# Lilypad_Schematic_1.net
KiCad netlist of a schematic drawn in Altium Designer
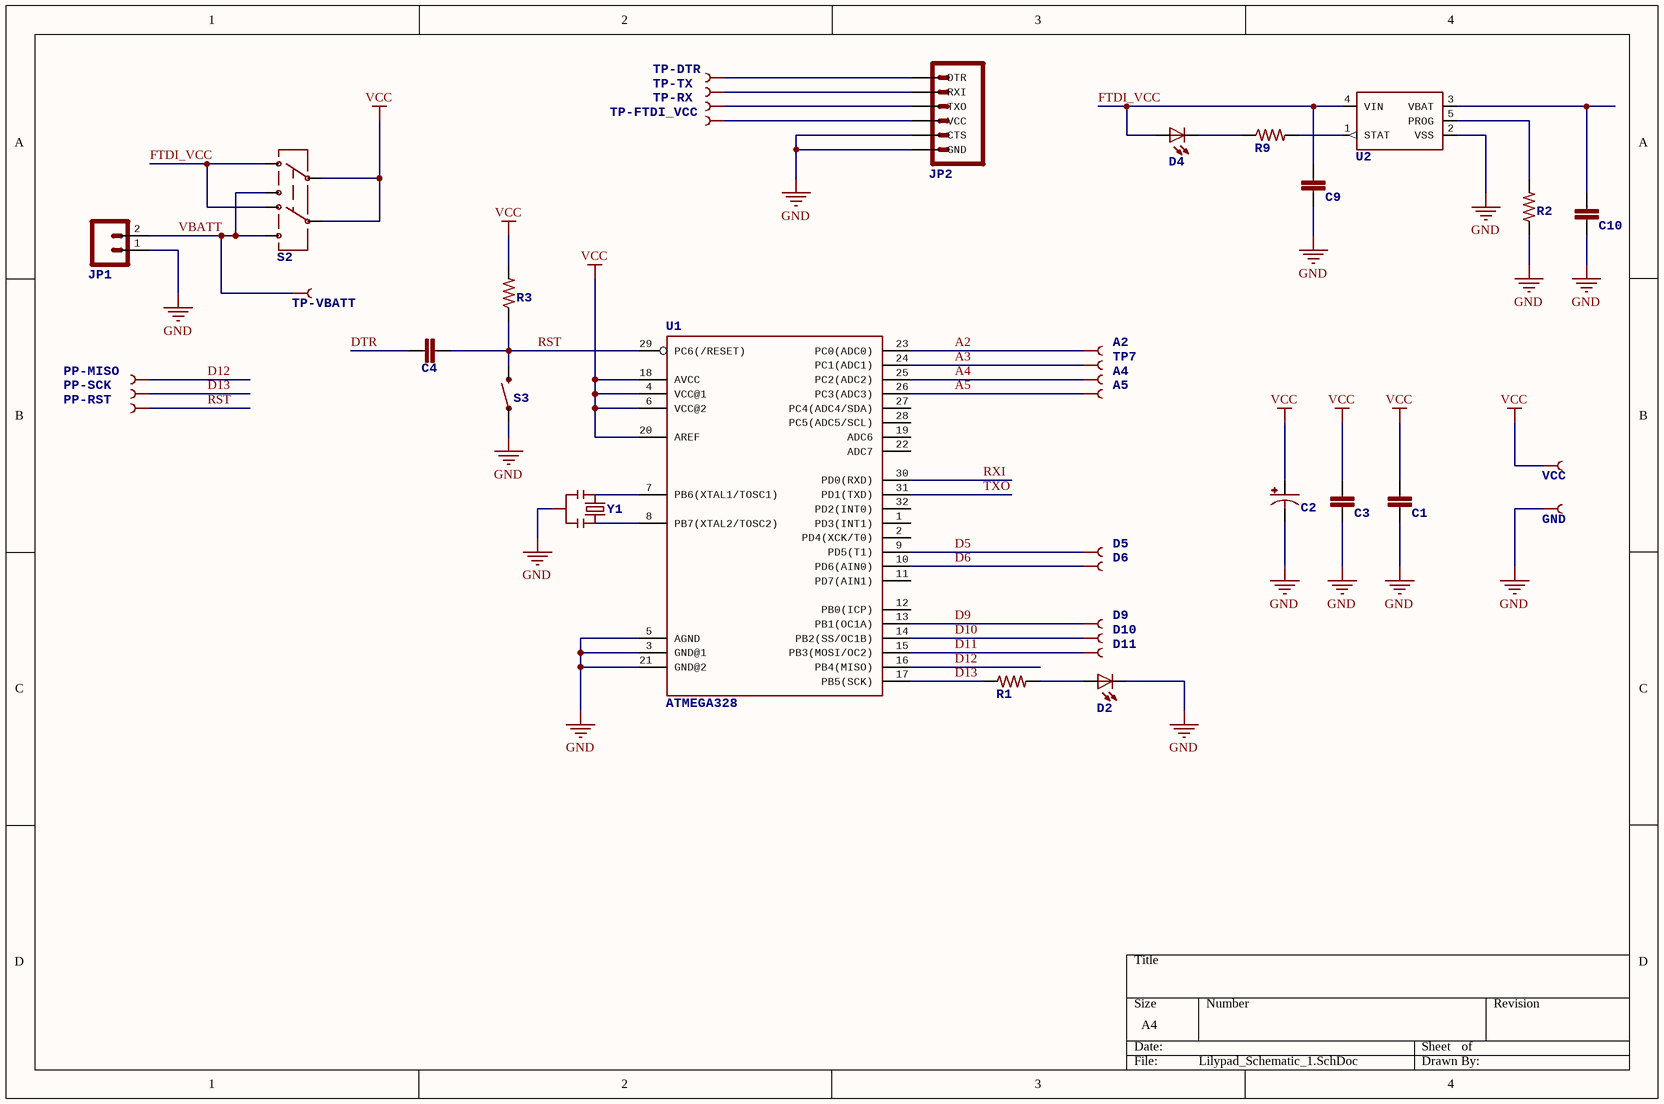
[diagram p0: Lilypad_Schematic_1.SchDoc]

(export (version "E")
  (design (tool "Eeschema 10.0.6"))
  (components
    (comp (ref "A2")
      (value "CONN")
      (footprint "PETAL-LONG-2")
      (libsource (lib "LilyPad Simple v2") (part "CONN"))
    )
    (comp (ref "A4")
      (value "CONN")
      (footprint "PETAL-LONG-2")
      (libsource (lib "LilyPad Simple v2") (part "CONN"))
    )
    (comp (ref "A5")
      (value "CONN")
      (footprint "PETAL-LONG-2")
      (libsource (lib "LilyPad Simple v2") (part "CONN"))
    )
    (comp (ref "C1")
      (value "CAP0402-CAP")
      (footprint "0402-CAP")
      (libsource (lib "LilyPad Simple v2") (part "CAP0402-CAP"))
    )
    (comp (ref "C2")
      (value "CAP_POL3528")
      (footprint "EIA3528")
      (libsource (lib "LilyPad Simple v2") (part "CAP_POL3528"))
    )
    (comp (ref "C3")
      (value "CAP0402-CAP")
      (footprint "0402-CAP")
      (libsource (lib "LilyPad Simple v2") (part "CAP0402-CAP"))
    )
    (comp (ref "C4") (value "CAP0402-CAP") (footprint "0402-CAP") (libsource (lib "") (part "CAP0402-CAP_1")))
    (comp (ref "C9")
      (value "CAP0402-CAP")
      (footprint "0402-CAP")
      (libsource (lib "LilyPad Simple v2") (part "CAP0402-CAP"))
    )
    (comp (ref "C10")
      (value "CAP0402-CAP")
      (footprint "0402-CAP")
      (libsource (lib "LilyPad Simple v2") (part "CAP0402-CAP"))
    )
    (comp (ref "D2")
      (value "LED0603")
      (footprint "LED-0603")
      (libsource (lib "LilyPad Simple v2") (part "LED0603"))
    )
    (comp (ref "D4")
      (value "LED0603")
      (footprint "LED-0603")
      (libsource (lib "LilyPad Simple v2") (part "LED0603"))
    )
    (comp (ref "D5")
      (value "CONN")
      (footprint "PETAL-LONG-2")
      (libsource (lib "LilyPad Simple v2") (part "CONN"))
    )
    (comp (ref "D6")
      (value "CONN")
      (footprint "PETAL-LONG-2")
      (libsource (lib "LilyPad Simple v2") (part "CONN"))
    )
    (comp (ref "D9")
      (value "CONN")
      (footprint "PETAL-LONG-2")
      (libsource (lib "LilyPad Simple v2") (part "CONN"))
    )
    (comp (ref "D10")
      (value "CONN")
      (footprint "PETAL-LONG-2")
      (libsource (lib "LilyPad Simple v2") (part "CONN"))
    )
    (comp (ref "D11")
      (value "CONN")
      (footprint "PETAL-LONG-2")
      (libsource (lib "LilyPad Simple v2") (part "CONN"))
    )
    (comp (ref "GND")
      (value "CONN")
      (footprint "PETAL-LONG-2")
      (libsource (lib "LilyPad Simple v2") (part "CONN"))
    )
    (comp (ref "JP1")
      (value "M02-JST-2MM-SMT")
      (footprint "JST-2-SMD")
      (libsource (lib "LilyPad Simple v2") (part "M02-JST-2MM-SMT"))
    )
    (comp (ref "JP2")
      (value "ARDUINO_SERIAL_PROGRAMSMD")
      (footprint "1X06-SMD")
      (libsource (lib "LilyPad Simple v2") (part "ARDUINO_SERIAL_PROGRAMSMD"))
    )
    (comp (ref "PP-MISO")
      (value "TEST-POINT3X5")
      (footprint "PAD.03X.05")
      (libsource (lib "LilyPad Simple v2") (part "TEST-POINT3X5"))
    )
    (comp (ref "PP-RST")
      (value "TEST-POINT3X5")
      (footprint "PAD.03X.05")
      (libsource (lib "LilyPad Simple v2") (part "TEST-POINT3X5"))
    )
    (comp (ref "PP-SCK")
      (value "TEST-POINT3X5")
      (footprint "PAD.03X.05")
      (libsource (lib "LilyPad Simple v2") (part "TEST-POINT3X5"))
    )
    (comp (ref "R1")
      (value "RESISTOR0402-RES")
      (footprint "0402-RES")
      (libsource (lib "LilyPad Simple v2") (part "RESISTOR0402-RES"))
    )
    (comp (ref "R2")
      (value "RESISTOR0402-RES")
      (footprint "0402-RES")
      (libsource (lib "LilyPad Simple v2") (part "RESISTOR0402-RES"))
    )
    (comp (ref "R3")
      (value "RESISTOR0402-RES")
      (footprint "0402-RES")
      (libsource (lib "LilyPad Simple v2") (part "RESISTOR0402-RES"))
    )
    (comp (ref "R9")
      (value "RESISTOR0402-RES")
      (footprint "0402-RES")
      (libsource (lib "LilyPad Simple v2") (part "RESISTOR0402-RES"))
    )
    (comp (ref "S2")
      (value "AYZ0202")
      (footprint "AYZ0202")
      (libsource (lib "LilyPad Simple v2") (part "AYZ0202"))
    )
    (comp (ref "S3")
      (value "SWITCH-MOMENTARY-2SMD-2")
      (footprint "TACTILE_SWITCH_SMD-2")
      (libsource (lib "LilyPad Simple v2") (part "SWITCH-MOMENTARY-2SMD-2"))
    )
    (comp (ref "TP-DTR")
      (value "TEST-POINT3X5")
      (footprint "PAD.03X.05")
      (libsource (lib "LilyPad Simple v2") (part "TEST-POINT3X5"))
    )
    (comp (ref "TP-FTDI_VCC")
      (value "TEST-POINT3X5")
      (footprint "PAD.03X.05")
      (libsource (lib "LilyPad Simple v2") (part "TEST-POINT3X5"))
    )
    (comp (ref "TP-RX")
      (value "TEST-POINT3X5")
      (footprint "PAD.03X.05")
      (libsource (lib "LilyPad Simple v2") (part "TEST-POINT3X5"))
    )
    (comp (ref "TP-TX")
      (value "TEST-POINT3X5")
      (footprint "PAD.03X.05")
      (libsource (lib "LilyPad Simple v2") (part "TEST-POINT3X5"))
    )
    (comp (ref "TP-VBATT")
      (value "TEST-POINT3X5")
      (footprint "PAD.03X.05")
      (libsource (lib "LilyPad Simple v2") (part "TEST-POINT3X5"))
    )
    (comp (ref "TP7")
      (value "CONN")
      (footprint "PETAL-LONG-2")
      (libsource (lib "LilyPad Simple v2") (part "CONN"))
    )
    (comp (ref "U1")
      (value "ATMEGA328")
      (footprint "TQFP32-08")
      (libsource (lib "LilyPad Simple v2") (part "ATMEGA328"))
    )
    (comp (ref "U2")
      (value "MCP73831")
      (footprint "SOT23-5")
      (libsource (lib "LilyPad Simple v2") (part "MCP73831"))
    )
    (comp (ref "VCC")
      (value "CONN")
      (footprint "PETAL-LONG-2")
      (libsource (lib "LilyPad Simple v2") (part "CONN"))
    )
    (comp (ref "Y1")
      (value "RESONATORSMD")
      (footprint "RESONATOR-SMD")
      (libsource (lib "LilyPad Simple v2") (part "RESONATORSMD"))
    )
  )
  (nets
    (net (code "1") (name "/A2") (class "Default")
      (node (ref "A2") (pin "1") (pinfunction "1_1") (pintype "passive"))
      (node (ref "U1") (pin "23") (pinfunction "PC0(ADC0)_23") (pintype "passive"))
    )
    (net (code "2") (name "/A3") (class "Default")
      (node (ref "TP7") (pin "1") (pinfunction "1_1") (pintype "passive"))
      (node (ref "U1") (pin "24") (pinfunction "PC1(ADC1)_24") (pintype "passive"))
    )
    (net (code "3") (name "/A4") (class "Default")
      (node (ref "A4") (pin "1") (pinfunction "1_1") (pintype "passive"))
      (node (ref "U1") (pin "25") (pinfunction "PC2(ADC2)_25") (pintype "passive"))
    )
    (net (code "4") (name "/A5") (class "Default")
      (node (ref "A5") (pin "1") (pinfunction "1_1") (pintype "passive"))
      (node (ref "U1") (pin "26") (pinfunction "PC3(ADC3)_26") (pintype "passive"))
    )
    (net (code "5") (name "/D5") (class "Default")
      (node (ref "D5") (pin "1") (pinfunction "1_1") (pintype "passive"))
      (node (ref "U1") (pin "9") (pinfunction "PD5(T1)_9") (pintype "passive"))
    )
    (net (code "6") (name "/D6") (class "Default")
      (node (ref "D6") (pin "1") (pinfunction "1_1") (pintype "passive"))
      (node (ref "U1") (pin "10") (pinfunction "PD6(AIN0)_10") (pintype "passive"))
    )
    (net (code "7") (name "/D9") (class "Default")
      (node (ref "D9") (pin "1") (pinfunction "1_1") (pintype "passive"))
      (node (ref "U1") (pin "13") (pinfunction "PB1(OC1A)_13") (pintype "passive"))
    )
    (net (code "8") (name "/D10") (class "Default")
      (node (ref "D10") (pin "1") (pinfunction "1_1") (pintype "passive"))
      (node (ref "U1") (pin "14") (pinfunction "PB2(SS/OC1B)_14") (pintype "passive"))
    )
    (net (code "9") (name "/D11") (class "Default")
      (node (ref "D11") (pin "1") (pinfunction "1_1") (pintype "passive"))
      (node (ref "U1") (pin "15") (pinfunction "PB3(MOSI/OC2)_15") (pintype "passive"))
    )
    (net (code "10") (name "/D12") (class "Default")
      (node (ref "PP-MISO") (pin "P$1") (pinfunction "1_P$1") (pintype "passive"))
      (node (ref "U1") (pin "16") (pinfunction "PB4(MISO)_16") (pintype "passive"))
    )
    (net (code "11") (name "/D13") (class "Default")
      (node (ref "PP-SCK") (pin "P$1") (pinfunction "1_P$1") (pintype "passive"))
      (node (ref "R1") (pin "1") (pinfunction "1_1") (pintype "passive"))
      (node (ref "U1") (pin "17") (pinfunction "PB5(SCK)_17") (pintype "passive"))
    )
    (net (code "12") (name "/DTR") (class "Default")
      (node (ref "C4") (pin "1") (pinfunction "1_1") (pintype "passive"))
    )
    (net (code "13") (name "/FTDI_VCC") (class "Default")
      (node (ref "C9") (pin "1") (pinfunction "1_1") (pintype "passive"))
      (node (ref "D4") (pin "A") (pinfunction "A_A") (pintype "passive"))
      (node (ref "S2") (pin "3") (pinfunction "1_3") (pintype "passive"))
      (node (ref "S2") (pin "6") (pinfunction "4_6") (pintype "passive"))
      (node (ref "U2") (pin "4") (pinfunction "VIN_4") (pintype "power_in"))
    )
    (net (code "14") (name "/RST") (class "Default")
      (node (ref "C4") (pin "2") (pinfunction "2_2") (pintype "passive"))
      (node (ref "PP-RST") (pin "P$1") (pinfunction "1_P$1") (pintype "passive"))
      (node (ref "R3") (pin "1") (pinfunction "1_1") (pintype "passive"))
      (node (ref "S3") (pin "1") (pinfunction "2_1") (pintype "passive"))
      (node (ref "U1") (pin "29") (pinfunction "PC6(/RESET)_29") (pintype "passive"))
    )
    (net (code "15") (name "/RXI") (class "Default")
      (node (ref "U1") (pin "30") (pinfunction "PD0(RXD)_30") (pintype "passive"))
    )
    (net (code "16") (name "/TXO") (class "Default")
      (node (ref "U1") (pin "31") (pinfunction "PD1(TXD)_31") (pintype "passive"))
    )
    (net (code "17") (name "/VBATT") (class "Default")
      (node (ref "JP1") (pin "2") (pinfunction "2_2") (pintype "passive"))
      (node (ref "S2") (pin "1") (pinfunction "3_1") (pintype "passive"))
      (node (ref "S2") (pin "4") (pinfunction "6_4") (pintype "passive"))
      (node (ref "TP-VBATT") (pin "P$1") (pinfunction "1_P$1") (pintype "passive"))
    )
    (net (code "18") (name "GND") (class "Default")
      (node (ref "C1") (pin "2") (pinfunction "2_2") (pintype "passive"))
      (node (ref "C10") (pin "2") (pinfunction "2_2") (pintype "passive"))
      (node (ref "C2") (pin "C") (pinfunction "-_C") (pintype "passive"))
      (node (ref "C3") (pin "2") (pinfunction "2_2") (pintype "passive"))
      (node (ref "C9") (pin "2") (pinfunction "2_2") (pintype "passive"))
      (node (ref "D2") (pin "C") (pinfunction "C_C") (pintype "passive"))
      (node (ref "GND") (pin "1") (pinfunction "1_1") (pintype "passive"))
      (node (ref "JP1") (pin "1") (pinfunction "1_1") (pintype "passive"))
      (node (ref "JP2") (pin "5") (pinfunction "CTS_5") (pintype "passive"))
      (node (ref "JP2") (pin "6") (pinfunction "GND_6") (pintype "passive"))
      (node (ref "R2") (pin "1") (pinfunction "1_1") (pintype "passive"))
      (node (ref "S3") (pin "2") (pinfunction "1_2") (pintype "passive"))
      (node (ref "U1") (pin "21") (pinfunction "GND@2_21") (pintype "passive"))
      (node (ref "U1") (pin "3") (pinfunction "GND@1_3") (pintype "passive"))
      (node (ref "U1") (pin "5") (pinfunction "AGND_5") (pintype "passive"))
      (node (ref "U2") (pin "2") (pinfunction "VSS_2") (pintype "power_in"))
      (node (ref "Y1") (pin "2") (pinfunction "2_2") (pintype "passive"))
    )
    (net (code "19") (name "Net-(D2-PadA)") (class "Default")
      (node (ref "D2") (pin "A") (pinfunction "A_A") (pintype "passive"))
      (node (ref "R1") (pin "2") (pinfunction "2_2") (pintype "passive"))
    )
    (net (code "20") (name "Net-(D4-PadC)") (class "Default")
      (node (ref "D4") (pin "C") (pinfunction "C_C") (pintype "passive"))
      (node (ref "R9") (pin "1") (pinfunction "1_1") (pintype "passive"))
    )
    (net (code "21") (name "Net-(JP2-DTR)") (class "Default")
      (node (ref "JP2") (pin "1") (pinfunction "DTR_1") (pintype "passive"))
      (node (ref "TP-DTR") (pin "P$1") (pinfunction "1_P$1") (pintype "passive"))
    )
    (net (code "22") (name "Net-(JP2-RXI)") (class "Default")
      (node (ref "JP2") (pin "2") (pinfunction "RXI_2") (pintype "passive"))
      (node (ref "TP-TX") (pin "P$1") (pinfunction "1_P$1") (pintype "passive"))
    )
    (net (code "23") (name "Net-(JP2-TXO)") (class "Default")
      (node (ref "JP2") (pin "3") (pinfunction "TXO_3") (pintype "passive"))
      (node (ref "TP-RX") (pin "P$1") (pinfunction "1_P$1") (pintype "passive"))
    )
    (net (code "24") (name "Net-(JP2-VCC)") (class "Default")
      (node (ref "JP2") (pin "4") (pinfunction "VCC_4") (pintype "passive"))
      (node (ref "TP-FTDI_VCC") (pin "P$1") (pinfunction "1_P$1") (pintype "passive"))
    )
    (net (code "25") (name "Net-(U1-PB6(XTAL1{slash}TOSC1))") (class "Default")
      (node (ref "U1") (pin "7") (pinfunction "PB6(XTAL1/TOSC1)_7") (pintype "passive"))
      (node (ref "Y1") (pin "1") (pinfunction "1_1") (pintype "passive"))
    )
    (net (code "26") (name "Net-(U1-PB7(XTAL2{slash}TOSC2))") (class "Default")
      (node (ref "U1") (pin "8") (pinfunction "PB7(XTAL2/TOSC2)_8") (pintype "passive"))
      (node (ref "Y1") (pin "3") (pinfunction "3_3") (pintype "passive"))
    )
    (net (code "27") (name "Net-(U2-PROG)") (class "Default")
      (node (ref "R2") (pin "2") (pinfunction "2_2") (pintype "passive"))
      (node (ref "U2") (pin "5") (pinfunction "PROG_5") (pintype "passive"))
    )
    (net (code "28") (name "Net-(U2-STAT)") (class "Default")
      (node (ref "R9") (pin "2") (pinfunction "2_2") (pintype "passive"))
      (node (ref "U2") (pin "1") (pinfunction "STAT_1") (pintype "output"))
    )
    (net (code "29") (name "Net-(U2-VBAT)") (class "Default")
      (node (ref "C10") (pin "1") (pinfunction "1_1") (pintype "passive"))
      (node (ref "U2") (pin "3") (pinfunction "VBAT_3") (pintype "power_in"))
    )
    (net (code "30") (name "VCC") (class "Default")
      (node (ref "C1") (pin "1") (pinfunction "1_1") (pintype "passive"))
      (node (ref "C2") (pin "A") (pinfunction "+_A") (pintype "passive"))
      (node (ref "C3") (pin "1") (pinfunction "1_1") (pintype "passive"))
      (node (ref "R3") (pin "2") (pinfunction "2_2") (pintype "passive"))
      (node (ref "S2") (pin "2") (pinfunction "2_2") (pintype "passive"))
      (node (ref "S2") (pin "5") (pinfunction "5_5") (pintype "passive"))
      (node (ref "U1") (pin "18") (pinfunction "AVCC_18") (pintype "passive"))
      (node (ref "U1") (pin "20") (pinfunction "AREF_20") (pintype "passive"))
      (node (ref "U1") (pin "4") (pinfunction "VCC@1_4") (pintype "passive"))
      (node (ref "U1") (pin "6") (pinfunction "VCC@2_6") (pintype "passive"))
      (node (ref "VCC") (pin "1") (pinfunction "1_1") (pintype "passive"))
    )
    (net (code "31") (name "unconnected-(U1-ADC6-Pad19)") (class "Default")
      (node (ref "U1") (pin "19") (pinfunction "ADC6_19") (pintype "passive"))
    )
    (net (code "32") (name "unconnected-(U1-ADC7-Pad22)") (class "Default")
      (node (ref "U1") (pin "22") (pinfunction "ADC7_22") (pintype "passive"))
    )
    (net (code "33") (name "unconnected-(U1-PB0(ICP)-Pad12)") (class "Default")
      (node (ref "U1") (pin "12") (pinfunction "PB0(ICP)_12") (pintype "passive"))
    )
    (net (code "34") (name "unconnected-(U1-PC4(ADC4{slash}SDA)-Pad27)") (class "Default")
      (node (ref "U1") (pin "27") (pinfunction "PC4(ADC4/SDA)_27") (pintype "passive"))
    )
    (net (code "35") (name "unconnected-(U1-PC5(ADC5{slash}SCL)-Pad28)") (class "Default")
      (node (ref "U1") (pin "28") (pinfunction "PC5(ADC5/SCL)_28") (pintype "passive"))
    )
    (net (code "36") (name "unconnected-(U1-PD2(INT0)-Pad32)") (class "Default")
      (node (ref "U1") (pin "32") (pinfunction "PD2(INT0)_32") (pintype "passive"))
    )
    (net (code "37") (name "unconnected-(U1-PD3(INT1)-Pad1)") (class "Default")
      (node (ref "U1") (pin "1") (pinfunction "PD3(INT1)_1") (pintype "passive"))
    )
    (net (code "38") (name "unconnected-(U1-PD4(XCK{slash}T0)-Pad2)") (class "Default")
      (node (ref "U1") (pin "2") (pinfunction "PD4(XCK/T0)_2") (pintype "passive"))
    )
    (net (code "39") (name "unconnected-(U1-PD7(AIN1)-Pad11)") (class "Default")
      (node (ref "U1") (pin "11") (pinfunction "PD7(AIN1)_11") (pintype "passive"))
    )
  )
)
